# USBtoUART_R.net
KiCad netlist of a schematic drawn in Altium Designer
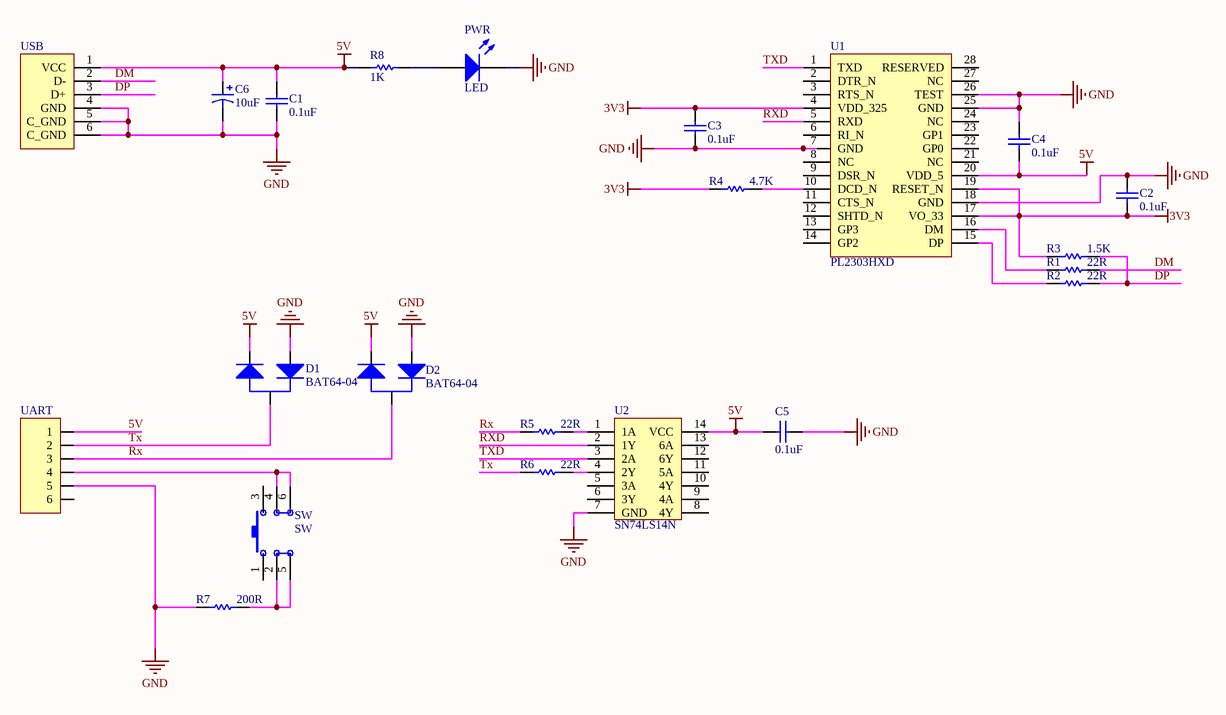
[diagram p0: USBtoUART R.SchDoc]

(export (version "E")
  (design (tool "Eeschema 10.0.6"))
  (components
    (comp (ref "C1") (value "0.1uF") (footprint "0603INCH_1608mm") (libsource (lib "Schlib1") (part "Cap")))
    (comp (ref "C2") (value "0.1uF") (footprint "0603INCH_1608mm") (libsource (lib "Schlib1") (part "Cap")))
    (comp (ref "C3") (value "0.1uF") (footprint "0603INCH_1608mm") (libsource (lib "Schlib1") (part "Cap")))
    (comp (ref "C4") (value "0.1uF") (footprint "0603INCH_1608mm") (libsource (lib "Schlib1") (part "Cap")))
    (comp (ref "C5") (value "0.1uF") (footprint "0603INCH_1608mm") (libsource (lib "Schlib1") (part "Cap")))
    (comp (ref "C6") (value "10uF") (footprint "7343-CAP") (libsource (lib "Schlib1") (part "Cap_Pol")))
    (comp (ref "D1")
      (value "BAT64-04")
      (footprint "SOT23_N")
      (libsource (lib "Integrated_Library1") (part "BAT64-04"))
    )
    (comp (ref "D2")
      (value "BAT64-04")
      (footprint "SOT23_N")
      (libsource (lib "Integrated_Library1") (part "BAT64-04"))
    )
    (comp (ref "PWR")
      (value "LED")
      (footprint "LED 0805")
      (libsource (lib "Integrated_Library1") (part "LED"))
    )
    (comp (ref "R1")
      (value "22R")
      (footprint "0603INCH_1608mm")
      (libsource (lib "Integrated_Library1") (part "Res"))
    )
    (comp (ref "R2")
      (value "22R")
      (footprint "0603INCH_1608mm")
      (libsource (lib "Integrated_Library1") (part "Res"))
    )
    (comp (ref "R3")
      (value "1.5K")
      (footprint "0603INCH_1608mm")
      (libsource (lib "Integrated_Library1") (part "Res"))
    )
    (comp (ref "R4")
      (value "4.7K")
      (footprint "0603INCH_1608mm")
      (libsource (lib "Integrated_Library1") (part "Res"))
    )
    (comp (ref "R5")
      (value "22R")
      (footprint "0603INCH_1608mm")
      (libsource (lib "Integrated_Library1") (part "Res"))
    )
    (comp (ref "R6")
      (value "22R")
      (footprint "0603INCH_1608mm")
      (libsource (lib "Integrated_Library1") (part "Res"))
    )
    (comp (ref "R7")
      (value "200R")
      (footprint "0603INCH_1608mm")
      (libsource (lib "Integrated_Library1") (part "Res"))
    )
    (comp (ref "R8")
      (value "1K")
      (footprint "0603INCH_1608mm")
      (libsource (lib "Integrated_Library1") (part "Res"))
    )
    (comp (ref "SW") (value "SW") (footprint "SW_zs") (libsource (lib "Schlib1") (part "SW_zs5.8")))
    (comp (ref "U1")
      (value "PL2303HXD")
      (footprint "SOP65P780-28BN")
      (libsource (lib "Schlib1") (part "PL2303HXD"))
    )
    (comp (ref "U2")
      (value "SN74LS14N")
      (footprint "PDIP_14pin")
      (libsource (lib "Schlib1") (part "74HC14D"))
    )
    (comp (ref "UART")
      (value "DP6")
      (footprint "Pin6_2.54mm")
      (libsource (lib "Integrated_Library1") (part "DP6"))
    )
    (comp (ref "USB")
      (value "USB")
      (footprint "USB2.5-2H4D")
      (libsource (lib "Integrated_Library1") (part "USB"))
    )
  )
  (nets
    (net (code "1") (name "/DM") (class "Default")
      (node (ref "R1") (pin "2") (pinfunction "2_2") (pintype "passive"))
      (node (ref "USB") (pin "2") (pinfunction "D-_2") (pintype "passive"))
    )
    (net (code "2") (name "/DP") (class "Default")
      (node (ref "R2") (pin "2") (pinfunction "2_2") (pintype "passive"))
      (node (ref "R3") (pin "1") (pinfunction "1_1") (pintype "passive"))
      (node (ref "USB") (pin "3") (pinfunction "D+_3") (pintype "passive"))
    )
    (net (code "3") (name "/RXD") (class "Default")
      (node (ref "U1") (pin "5") (pinfunction "RXD_5") (pintype "passive"))
      (node (ref "U2") (pin "2") (pinfunction "1Y_2") (pintype "passive"))
    )
    (net (code "4") (name "/Rx") (class "Default")
      (node (ref "D2") (pin "3") (pinfunction "3_3") (pintype "passive"))
      (node (ref "R5") (pin "1") (pinfunction "1_1") (pintype "passive"))
      (node (ref "UART") (pin "3") (pinfunction "3_3") (pintype "passive"))
    )
    (net (code "5") (name "/TXD") (class "Default")
      (node (ref "U1") (pin "1") (pinfunction "TXD_1") (pintype "passive"))
      (node (ref "U2") (pin "3") (pinfunction "2A_3") (pintype "passive"))
    )
    (net (code "6") (name "/Tx") (class "Default")
      (node (ref "D1") (pin "3") (pinfunction "3_3") (pintype "passive"))
      (node (ref "R6") (pin "1") (pinfunction "1_1") (pintype "passive"))
      (node (ref "UART") (pin "2") (pinfunction "2_2") (pintype "passive"))
    )
    (net (code "7") (name "3V3") (class "Default")
      (node (ref "C2") (pin "2") (pinfunction "2_2") (pintype "passive"))
      (node (ref "C3") (pin "2") (pinfunction "2_2") (pintype "passive"))
      (node (ref "R3") (pin "2") (pinfunction "2_2") (pintype "passive"))
      (node (ref "R4") (pin "1") (pinfunction "1_1") (pintype "passive"))
      (node (ref "U1") (pin "17") (pinfunction "VO_33_17") (pintype "passive"))
      (node (ref "U1") (pin "19") (pinfunction "RESET_N_19") (pintype "passive"))
      (node (ref "U1") (pin "4") (pinfunction "VDD_325_4") (pintype "passive"))
    )
    (net (code "8") (name "5V") (class "Default")
      (node (ref "C1") (pin "2") (pinfunction "2_2") (pintype "passive"))
      (node (ref "C4") (pin "1") (pinfunction "1_1") (pintype "passive"))
      (node (ref "C5") (pin "1") (pinfunction "1_1") (pintype "passive"))
      (node (ref "C6") (pin "1") (pinfunction "1_1") (pintype "passive"))
      (node (ref "D1") (pin "2") (pinfunction "2_2") (pintype "passive"))
      (node (ref "D2") (pin "2") (pinfunction "2_2") (pintype "passive"))
      (node (ref "R8") (pin "1") (pinfunction "1_1") (pintype "passive"))
      (node (ref "U1") (pin "20") (pinfunction "VDD_5_20") (pintype "passive"))
      (node (ref "U2") (pin "14") (pinfunction "VCC_14") (pintype "passive"))
      (node (ref "UART") (pin "1") (pinfunction "1_1") (pintype "passive"))
      (node (ref "USB") (pin "1") (pinfunction "VCC_1") (pintype "passive"))
    )
    (net (code "9") (name "GND") (class "Default")
      (node (ref "C1") (pin "1") (pinfunction "1_1") (pintype "passive"))
      (node (ref "C2") (pin "1") (pinfunction "1_1") (pintype "passive"))
      (node (ref "C3") (pin "1") (pinfunction "1_1") (pintype "passive"))
      (node (ref "C4") (pin "2") (pinfunction "2_2") (pintype "passive"))
      (node (ref "C5") (pin "2") (pinfunction "2_2") (pintype "passive"))
      (node (ref "C6") (pin "2") (pinfunction "2_2") (pintype "passive"))
      (node (ref "D1") (pin "1") (pinfunction "1_1") (pintype "passive"))
      (node (ref "D2") (pin "1") (pinfunction "1_1") (pintype "passive"))
      (node (ref "PWR") (pin "K") (pinfunction "2_K") (pintype "passive"))
      (node (ref "R7") (pin "1") (pinfunction "1_1") (pintype "passive"))
      (node (ref "U1") (pin "18") (pinfunction "GND_18") (pintype "passive"))
      (node (ref "U1") (pin "25") (pinfunction "GND_25") (pintype "passive"))
      (node (ref "U1") (pin "26") (pinfunction "TEST_26") (pintype "passive"))
      (node (ref "U1") (pin "7") (pinfunction "GND_7") (pintype "passive"))
      (node (ref "U2") (pin "7") (pinfunction "GND_7") (pintype "passive"))
      (node (ref "UART") (pin "5") (pinfunction "5_5") (pintype "passive"))
      (node (ref "USB") (pin "4") (pinfunction "GND_4") (pintype "passive"))
      (node (ref "USB") (pin "5") (pinfunction "C_GND_5") (pintype "passive"))
      (node (ref "USB") (pin "6") (pinfunction "C_GND_6") (pintype "passive"))
    )
    (net (code "10") (name "Net-(PWR-1)") (class "Default")
      (node (ref "PWR") (pin "A") (pinfunction "1_A") (pintype "passive"))
      (node (ref "R8") (pin "2") (pinfunction "2_2") (pintype "passive"))
    )
    (net (code "11") (name "Net-(R7-Pad2)") (class "Default")
      (node (ref "R7") (pin "2") (pinfunction "2_2") (pintype "passive"))
      (node (ref "SW") (pin "2") (pinfunction "2_2") (pintype "passive"))
      (node (ref "SW") (pin "5") (pinfunction "5_5") (pintype "passive"))
    )
    (net (code "12") (name "Net-(SW-Pad4)") (class "Default")
      (node (ref "SW") (pin "4") (pinfunction "4_4") (pintype "passive"))
      (node (ref "SW") (pin "6") (pinfunction "6_6") (pintype "passive"))
      (node (ref "UART") (pin "4") (pinfunction "4_4") (pintype "passive"))
    )
    (net (code "13") (name "Net-(U1-DCD_N)") (class "Default")
      (node (ref "R4") (pin "2") (pinfunction "2_2") (pintype "passive"))
      (node (ref "U1") (pin "10") (pinfunction "DCD_N_10") (pintype "passive"))
    )
    (net (code "14") (name "Net-(U1-DM)") (class "Default")
      (node (ref "R1") (pin "1") (pinfunction "1_1") (pintype "passive"))
      (node (ref "U1") (pin "16") (pinfunction "DM_16") (pintype "passive"))
    )
    (net (code "15") (name "Net-(U1-DP)") (class "Default")
      (node (ref "R2") (pin "1") (pinfunction "1_1") (pintype "passive"))
      (node (ref "U1") (pin "15") (pinfunction "DP_15") (pintype "passive"))
    )
    (net (code "16") (name "Net-(U2-1A)") (class "Default")
      (node (ref "R5") (pin "2") (pinfunction "2_2") (pintype "passive"))
      (node (ref "U2") (pin "1") (pinfunction "1A_1") (pintype "passive"))
    )
    (net (code "17") (name "Net-(U2-2Y)") (class "Default")
      (node (ref "R6") (pin "2") (pinfunction "2_2") (pintype "passive"))
      (node (ref "U2") (pin "4") (pinfunction "2Y_4") (pintype "passive"))
    )
    (net (code "18") (name "unconnected-(SW-Pad1)") (class "Default")
      (node (ref "SW") (pin "1") (pinfunction "1_1") (pintype "passive"))
    )
    (net (code "19") (name "unconnected-(SW-Pad3)") (class "Default")
      (node (ref "SW") (pin "3") (pinfunction "3_3") (pintype "passive"))
    )
    (net (code "20") (name "unconnected-(U1-CTS_N-Pad11)") (class "Default")
      (node (ref "U1") (pin "11") (pinfunction "CTS_N_11") (pintype "passive"))
    )
    (net (code "21") (name "unconnected-(U1-DSR_N-Pad9)") (class "Default")
      (node (ref "U1") (pin "9") (pinfunction "DSR_N_9") (pintype "passive"))
    )
    (net (code "22") (name "unconnected-(U1-DTR_N-Pad2)") (class "Default")
      (node (ref "U1") (pin "2") (pinfunction "DTR_N_2") (pintype "passive"))
    )
    (net (code "23") (name "unconnected-(U1-GP0-Pad22)") (class "Default")
      (node (ref "U1") (pin "22") (pinfunction "GP0_22") (pintype "passive"))
    )
    (net (code "24") (name "unconnected-(U1-GP1-Pad23)") (class "Default")
      (node (ref "U1") (pin "23") (pinfunction "GP1_23") (pintype "passive"))
    )
    (net (code "25") (name "unconnected-(U1-GP2-Pad14)") (class "Default")
      (node (ref "U1") (pin "14") (pinfunction "GP2_14") (pintype "passive"))
    )
    (net (code "26") (name "unconnected-(U1-GP3-Pad13)") (class "Default")
      (node (ref "U1") (pin "13") (pinfunction "GP3_13") (pintype "passive"))
    )
    (net (code "27") (name "unconnected-(U1-NC-Pad8)") (class "Default")
      (node (ref "U1") (pin "8") (pinfunction "NC_8") (pintype "passive"))
    )
    (net (code "28") (name "unconnected-(U1-NC-Pad21)") (class "Default")
      (node (ref "U1") (pin "21") (pinfunction "NC_21") (pintype "passive"))
    )
    (net (code "29") (name "unconnected-(U1-NC-Pad24)") (class "Default")
      (node (ref "U1") (pin "24") (pinfunction "NC_24") (pintype "passive"))
    )
    (net (code "30") (name "unconnected-(U1-NC-Pad27)") (class "Default")
      (node (ref "U1") (pin "27") (pinfunction "NC_27") (pintype "passive"))
    )
    (net (code "31") (name "unconnected-(U1-RESERVED-Pad28)") (class "Default")
      (node (ref "U1") (pin "28") (pinfunction "RESERVED_28") (pintype "passive"))
    )
    (net (code "32") (name "unconnected-(U1-RI_N-Pad6)") (class "Default")
      (node (ref "U1") (pin "6") (pinfunction "RI_N_6") (pintype "passive"))
    )
    (net (code "33") (name "unconnected-(U1-RTS_N-Pad3)") (class "Default")
      (node (ref "U1") (pin "3") (pinfunction "RTS_N_3") (pintype "passive"))
    )
    (net (code "34") (name "unconnected-(U1-SHTD_N-Pad12)") (class "Default")
      (node (ref "U1") (pin "12") (pinfunction "SHTD_N_12") (pintype "passive"))
    )
    (net (code "35") (name "unconnected-(U2-3A-Pad5)") (class "Default")
      (node (ref "U2") (pin "5") (pinfunction "3A_5") (pintype "passive"))
    )
    (net (code "36") (name "unconnected-(U2-3Y-Pad6)") (class "Default")
      (node (ref "U2") (pin "6") (pinfunction "3Y_6") (pintype "passive"))
    )
    (net (code "37") (name "unconnected-(U2-4A-Pad9)") (class "Default")
      (node (ref "U2") (pin "9") (pinfunction "4A_9") (pintype "passive"))
    )
    (net (code "38") (name "unconnected-(U2-4Y-Pad8)") (class "Default")
      (node (ref "U2") (pin "8") (pinfunction "4Y_8") (pintype "passive"))
    )
    (net (code "39") (name "unconnected-(U2-4Y-Pad10)") (class "Default")
      (node (ref "U2") (pin "10") (pinfunction "4Y_10") (pintype "passive"))
    )
    (net (code "40") (name "unconnected-(U2-5A-Pad11)") (class "Default")
      (node (ref "U2") (pin "11") (pinfunction "5A_11") (pintype "passive"))
    )
    (net (code "41") (name "unconnected-(U2-6A-Pad13)") (class "Default")
      (node (ref "U2") (pin "13") (pinfunction "6A_13") (pintype "passive"))
    )
    (net (code "42") (name "unconnected-(U2-6Y-Pad12)") (class "Default")
      (node (ref "U2") (pin "12") (pinfunction "6Y_12") (pintype "passive"))
    )
    (net (code "43") (name "unconnected-(UART-Pad6)") (class "Default")
      (node (ref "UART") (pin "6") (pinfunction "6_6") (pintype "passive"))
    )
  )
)
